# SCH_uCompute_NRF24L01_module_2026-03-19.net
KiCad netlist of a schematic drawn in EasyEDA
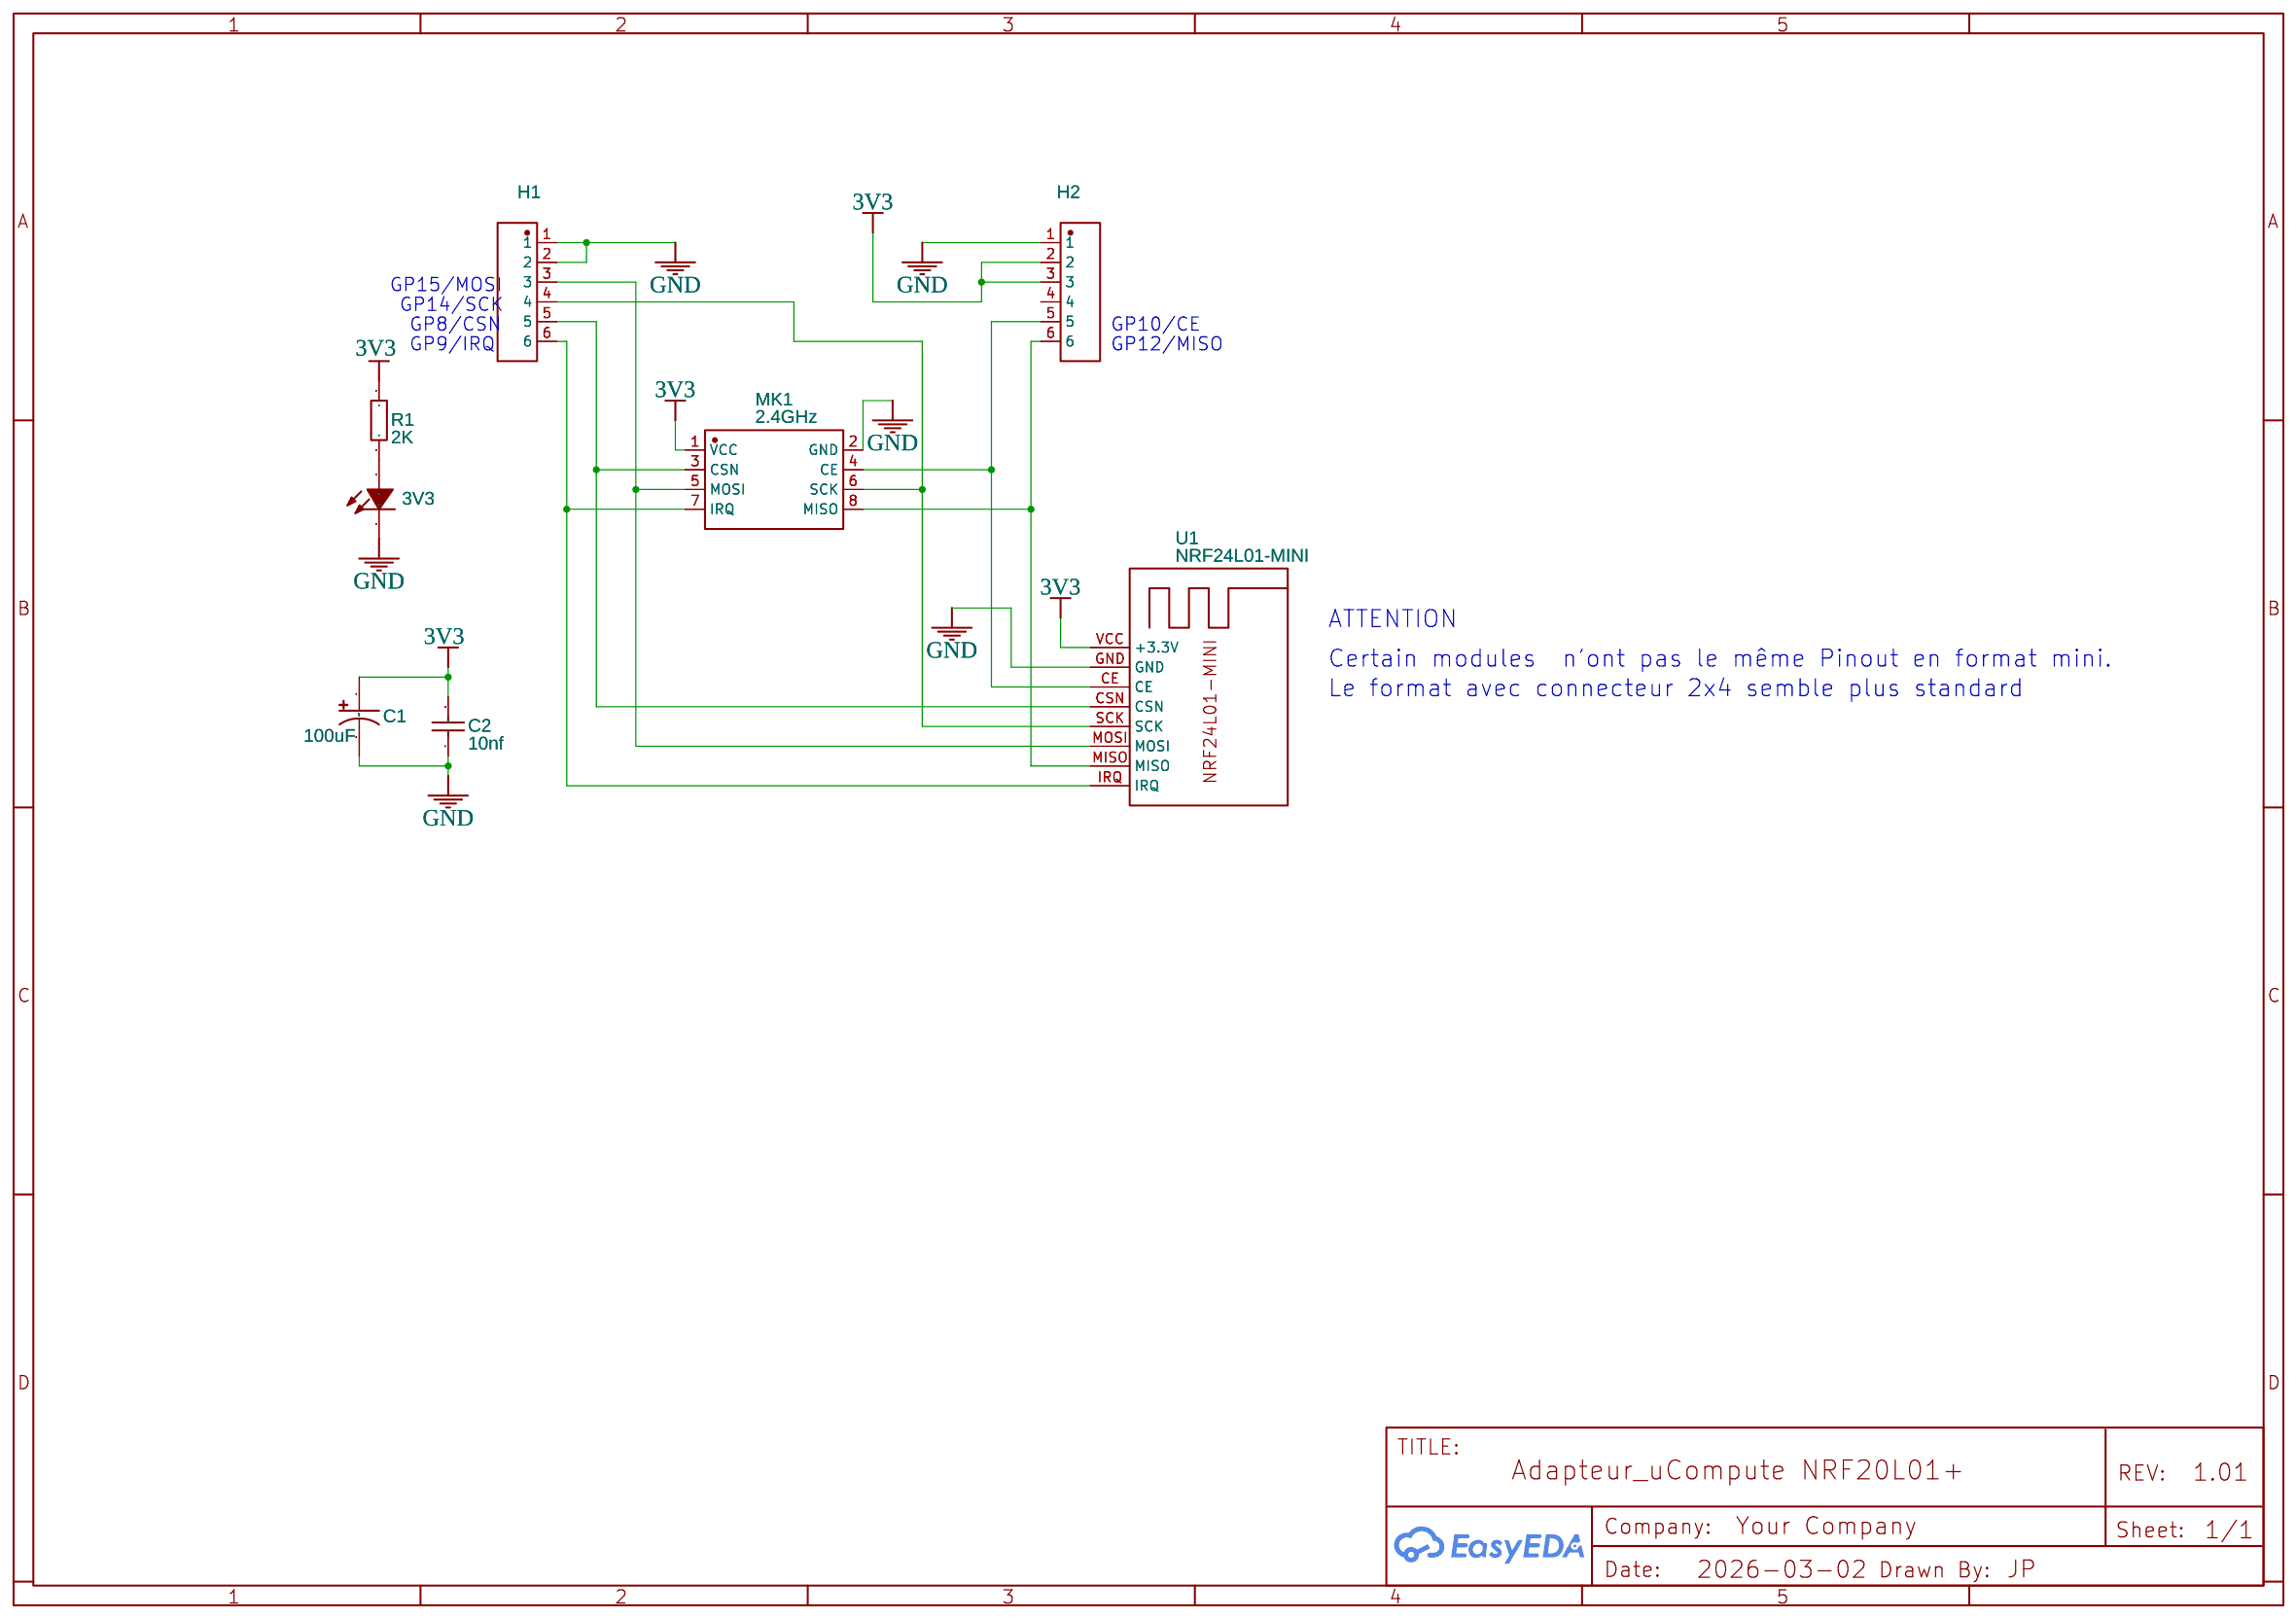
[diagram p0: schematic sheet]

(export (version "E")
  (design (tool "Eeschema 10.0.6"))
  (components
    (comp (ref "3V3")
      (value "XL-1206QPC")
      (fields (field (name "Manufacturer") "LCSC"))
      (libsource (lib "") (part "XL-1206QPC"))
    )
    (comp (ref "C1")
      (value "100uF")
      (fields
        (field (name "Manufacturer Part") "TLJA107M010R1400")
        (field (name "Manufacturer") "Kyocera AVX")
      )
      (libsource (lib "") (part "TLJA107M010R1400"))
    )
    (comp (ref "C2")
      (value "10nf")
      (fields (field (name "Manufacturer Part") "0805CG220J500NT") (field (name "Manufacturer") "FH"))
      (libsource (lib "") (part "0805CG220J500NT"))
    )
    (comp (ref "H1")
      (value "KH-2.54PH180-1X6P-L11.5")
      (fields (field (name "Manufacturer") "kinghelm(金航标)"))
      (libsource (lib "") (part "KH-2.54PH180-1X6P-L11.5"))
    )
    (comp (ref "H2")
      (value "KH-2.54PH180-1X6P-L11.5")
      (fields (field (name "Manufacturer") "kinghelm(金航标)"))
      (libsource (lib "") (part "KH-2.54PH180-1X6P-L11.5_1"))
    )
    (comp (ref "MK1")
      (value "2.4GHz")
      (fields (field (name "Manufacturer Part") "NF-04") (field (name "Manufacturer") "Ai-Thinker(安信可)"))
      (libsource (lib "") (part "NRF24L01"))
    )
    (comp (ref "R1")
      (value "2K")
      (fields (field (name "Manufacturer Part") "RC0805DR-071KL") (field (name "Manufacturer") "YAGEO(国巨)"))
      (libsource (lib "") (part "RC0805DR-071KL"))
    )
    (comp (ref "U1") (value "NRF24L01-MINI") (libsource (lib "") (part "NRF24L01-MINI")))
  )
  (nets
    (net (code "1") (name "3V3") (class "Default")
      (node (ref "C1") (pin "1") (pinfunction "1_1") (pintype "unspecified"))
      (node (ref "C2") (pin "2") (pinfunction "2_2") (pintype "input"))
      (node (ref "H2") (pin "2") (pinfunction "2_2") (pintype "unspecified"))
      (node (ref "H2") (pin "3") (pinfunction "3_3") (pintype "unspecified"))
      (node (ref "MK1") (pin "1") (pinfunction "VCC_1") (pintype "unspecified"))
      (node (ref "R1") (pin "1") (pinfunction "1_1") (pintype "unspecified"))
      (node (ref "U1") (pin "VCC") (pinfunction "+3.3V_VCC") (pintype "passive"))
    )
    (net (code "2") (name "GND") (class "Default")
      (node (ref "3V3") (pin "1") (pinfunction "K_1") (pintype "unspecified"))
      (node (ref "C1") (pin "2") (pinfunction "2_2") (pintype "unspecified"))
      (node (ref "C2") (pin "1") (pinfunction "1_1") (pintype "input"))
      (node (ref "H1") (pin "1") (pinfunction "1_1") (pintype "unspecified"))
      (node (ref "H1") (pin "2") (pinfunction "2_2") (pintype "unspecified"))
      (node (ref "H2") (pin "1") (pinfunction "1_1") (pintype "unspecified"))
      (node (ref "MK1") (pin "2") (pinfunction "GND_2") (pintype "unspecified"))
      (node (ref "U1") (pin "GND") (pinfunction "GND_GND") (pintype "unspecified"))
    )
    (net (code "3") (name "Net-(3V3-A)") (class "Default")
      (node (ref "3V3") (pin "2") (pinfunction "A_2") (pintype "unspecified"))
      (node (ref "R1") (pin "2") (pinfunction "2_2") (pintype "unspecified"))
    )
    (net (code "4") (name "Net-(MK1-CE)") (class "Default")
      (node (ref "H2") (pin "5") (pinfunction "5_5") (pintype "unspecified"))
      (node (ref "MK1") (pin "4") (pinfunction "CE_4") (pintype "unspecified"))
      (node (ref "U1") (pin "CE") (pinfunction "CE_CE") (pintype "bidirectional"))
    )
    (net (code "5") (name "Net-(MK1-CSN)") (class "Default")
      (node (ref "H1") (pin "5") (pinfunction "5_5") (pintype "unspecified"))
      (node (ref "MK1") (pin "3") (pinfunction "CSN_3") (pintype "unspecified"))
      (node (ref "U1") (pin "CSN") (pinfunction "CSN_CSN") (pintype "bidirectional"))
    )
    (net (code "6") (name "Net-(MK1-IRQ)") (class "Default")
      (node (ref "H1") (pin "6") (pinfunction "6_6") (pintype "unspecified"))
      (node (ref "MK1") (pin "7") (pinfunction "IRQ_7") (pintype "unspecified"))
      (node (ref "U1") (pin "IRQ") (pinfunction "IRQ_IRQ") (pintype "unspecified"))
    )
    (net (code "7") (name "Net-(MK1-MISO)") (class "Default")
      (node (ref "H2") (pin "6") (pinfunction "6_6") (pintype "unspecified"))
      (node (ref "MK1") (pin "8") (pinfunction "MISO_8") (pintype "unspecified"))
      (node (ref "U1") (pin "MISO") (pinfunction "MISO_MISO") (pintype "output"))
    )
    (net (code "8") (name "Net-(MK1-MOSI)") (class "Default")
      (node (ref "H1") (pin "3") (pinfunction "3_3") (pintype "unspecified"))
      (node (ref "MK1") (pin "5") (pinfunction "MOSI_5") (pintype "unspecified"))
      (node (ref "U1") (pin "MOSI") (pinfunction "MOSI_MOSI") (pintype "bidirectional"))
    )
    (net (code "9") (name "Net-(MK1-SCK)") (class "Default")
      (node (ref "H1") (pin "4") (pinfunction "4_4") (pintype "unspecified"))
      (node (ref "MK1") (pin "6") (pinfunction "SCK_6") (pintype "unspecified"))
      (node (ref "U1") (pin "SCK") (pinfunction "SCK_SCK") (pintype "bidirectional"))
    )
    (net (code "10") (name "unconnected-(H2-Pad4)") (class "Default")
      (node (ref "H2") (pin "4") (pinfunction "4_4") (pintype "unspecified"))
    )
  )
)
